# RFTX.net
KiCad netlist of a schematic drawn in Altium Designer
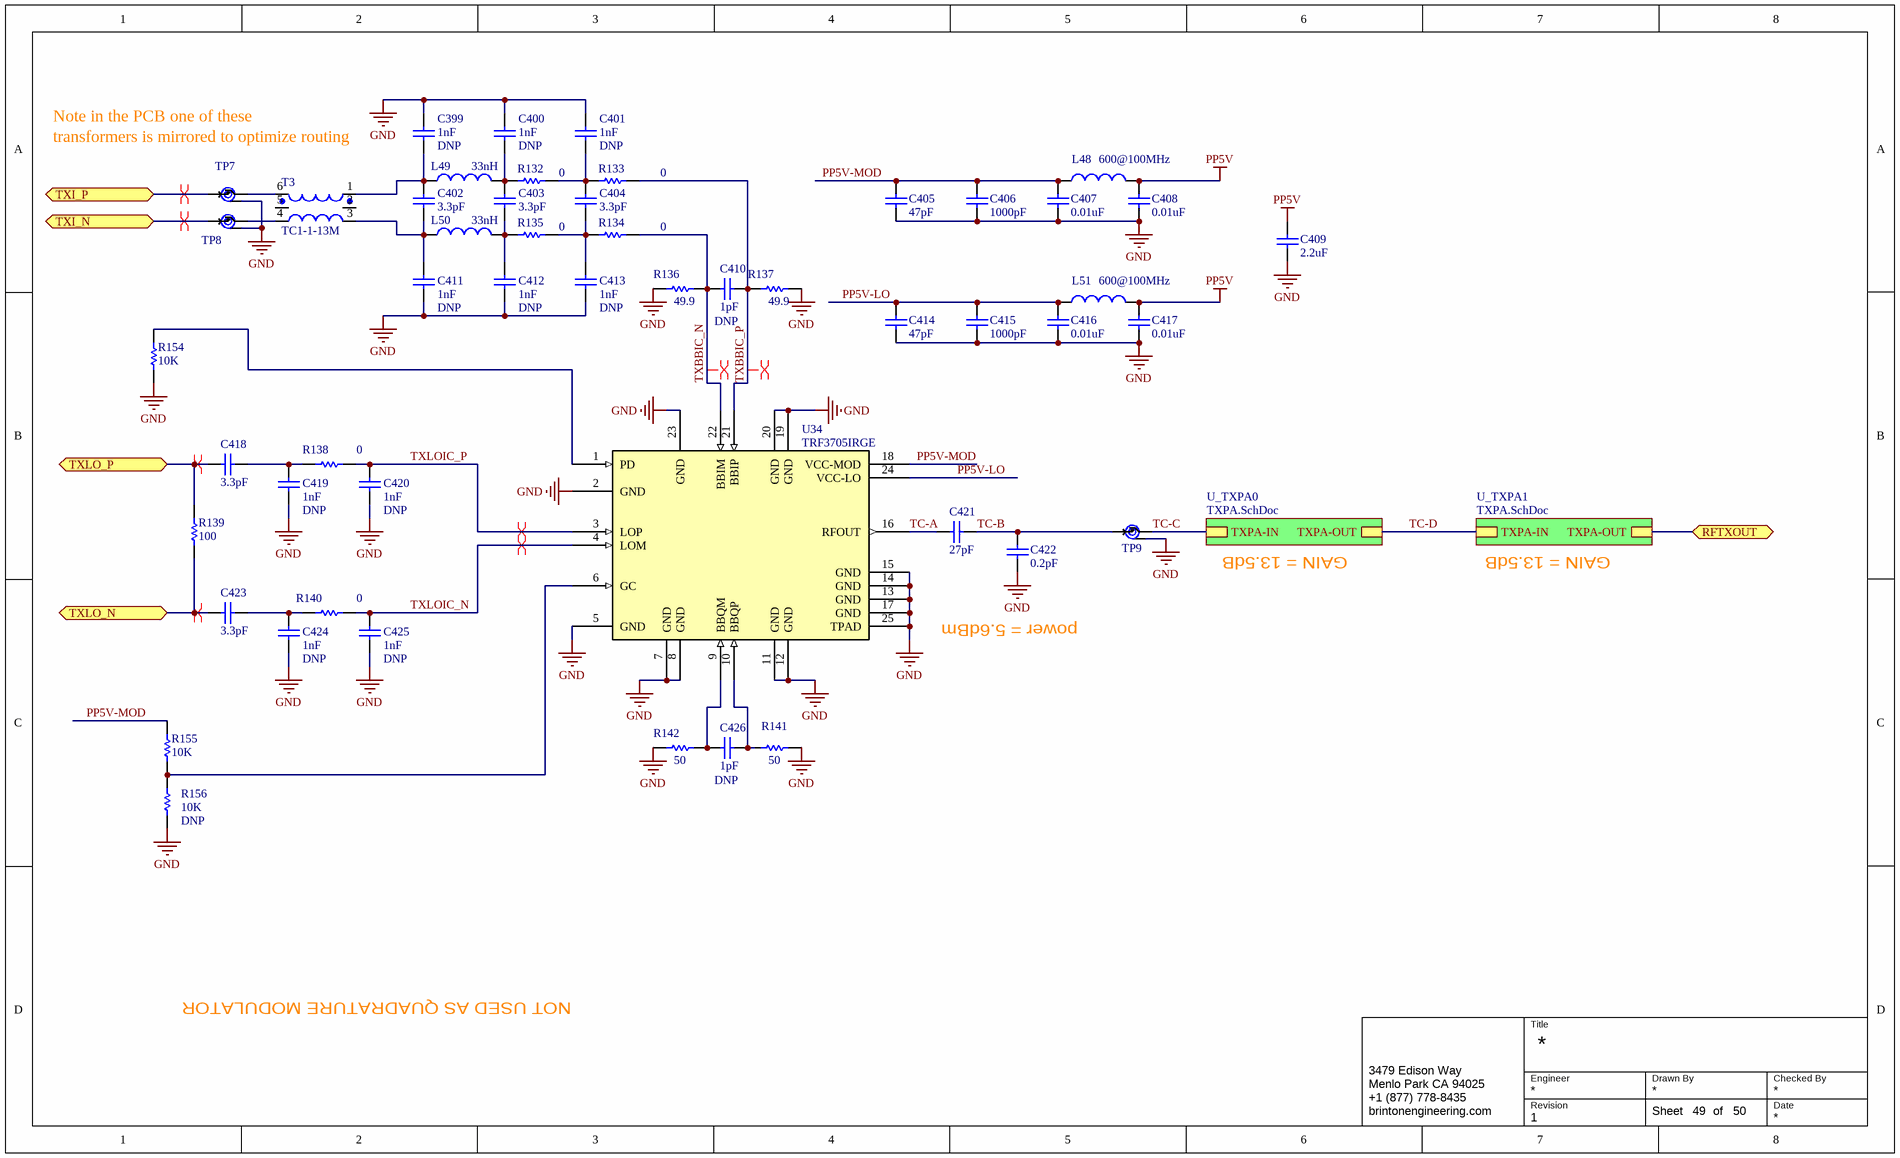
[diagram p0: RFTX.SchDoc]

(export (version "E")
  (design (tool "Eeschema 10.0.6"))
  (components
    (comp (ref "C399")
      (value "1nF")
      (footprint "0402")
      (description "CAP 0402")
      (fields (field (name "VOLTAGE") "16V") (field (name "DO NOT POPULATE") "DNP"))
      (libsource (lib "Graviton") (part "CAP 0402"))
    )
    (comp (ref "C400")
      (value "1nF")
      (footprint "0402")
      (description "CAP 0402")
      (fields (field (name "VOLTAGE") "16V") (field (name "DO NOT POPULATE") "DNP"))
      (libsource (lib "Graviton") (part "CAP 0402"))
    )
    (comp (ref "C401")
      (value "1nF")
      (footprint "0402")
      (description "CAP 0402")
      (fields (field (name "VOLTAGE") "16V") (field (name "DO NOT POPULATE") "DNP"))
      (libsource (lib "Graviton") (part "CAP 0402"))
    )
    (comp (ref "C402")
      (value "3.3pF")
      (footprint "0402")
      (description "CAP 0402")
      (fields (field (name "VOLTAGE") "50V") (field (name "MANUFACTURER") "Johanson Technology"))
      (libsource (lib "Graviton") (part "CAP 0402"))
    )
    (comp (ref "C403")
      (value "3.3pF")
      (footprint "0402")
      (description "CAP 0402")
      (fields (field (name "VOLTAGE") "50V") (field (name "MANUFACTURER") "Johanson Technology"))
      (libsource (lib "Graviton") (part "CAP 0402"))
    )
    (comp (ref "C404")
      (value "3.3pF")
      (footprint "0402")
      (description "CAP 0402")
      (fields (field (name "VOLTAGE") "50V") (field (name "MANUFACTURER") "Johanson Technology"))
      (libsource (lib "Graviton") (part "CAP 0402"))
    )
    (comp (ref "C405")
      (value "47pF")
      (footprint "0402")
      (description "CAP 0402")
      (fields (field (name "VOLTAGE") "25V") (field (name "MANUFACTURER") "Kemet"))
      (libsource (lib "Graviton") (part "CAP 0402"))
    )
    (comp (ref "C406")
      (value "1000pF")
      (footprint "0402")
      (description "CAP 0402")
      (fields (field (name "VOLTAGE") "50V") (field (name "MANUFACTURER") "Murata"))
      (libsource (lib "Graviton") (part "CAP 0402"))
    )
    (comp (ref "C407")
      (value "0.01uF")
      (footprint "0402")
      (description "CAP 0402")
      (fields (field (name "VOLTAGE") "25V") (field (name "MANUFACTURER") "Murata"))
      (libsource (lib "Graviton") (part "CAP 0402"))
    )
    (comp (ref "C408")
      (value "0.01uF")
      (footprint "0402")
      (description "CAP 0402")
      (fields (field (name "VOLTAGE") "25V") (field (name "MANUFACTURER") "Murata"))
      (libsource (lib "Graviton") (part "CAP 0402"))
    )
    (comp (ref "C409")
      (value "2.2uF")
      (footprint "1206")
      (description "CAP 0402")
      (fields (field (name "VOLTAGE") "16V") (field (name "MANUFACTURER") "Kemet"))
      (libsource (lib "Graviton") (part "CAP 0402"))
    )
    (comp (ref "C410")
      (value "1pF")
      (footprint "0402")
      (description "CAP 0402")
      (fields (field (name "VOLTAGE") "16V") (field (name "DO NOT POPULATE") "DNP"))
      (libsource (lib "Graviton") (part "CAP 0402"))
    )
    (comp (ref "C411")
      (value "1nF")
      (footprint "0402")
      (description "CAP 0402")
      (fields (field (name "VOLTAGE") "16V") (field (name "DO NOT POPULATE") "DNP"))
      (libsource (lib "Graviton") (part "CAP 0402"))
    )
    (comp (ref "C412")
      (value "1nF")
      (footprint "0402")
      (description "CAP 0402")
      (fields (field (name "VOLTAGE") "16V") (field (name "DO NOT POPULATE") "DNP"))
      (libsource (lib "Graviton") (part "CAP 0402"))
    )
    (comp (ref "C413")
      (value "1nF")
      (footprint "0402")
      (description "CAP 0402")
      (fields (field (name "VOLTAGE") "16V") (field (name "DO NOT POPULATE") "DNP"))
      (libsource (lib "Graviton") (part "CAP 0402"))
    )
    (comp (ref "C414")
      (value "47pF")
      (footprint "0402")
      (description "CAP 0402")
      (fields (field (name "VOLTAGE") "25V") (field (name "MANUFACTURER") "Kemet"))
      (libsource (lib "Graviton") (part "CAP 0402"))
    )
    (comp (ref "C415")
      (value "1000pF")
      (footprint "0402")
      (description "CAP 0402")
      (fields (field (name "VOLTAGE") "50V") (field (name "MANUFACTURER") "Murata"))
      (libsource (lib "Graviton") (part "CAP 0402"))
    )
    (comp (ref "C416")
      (value "0.01uF")
      (footprint "0402")
      (description "CAP 0402")
      (fields (field (name "VOLTAGE") "25V") (field (name "MANUFACTURER") "Murata"))
      (libsource (lib "Graviton") (part "CAP 0402"))
    )
    (comp (ref "C417")
      (value "0.01uF")
      (footprint "0402")
      (description "CAP 0402")
      (fields (field (name "VOLTAGE") "25V") (field (name "MANUFACTURER") "Murata"))
      (libsource (lib "Graviton") (part "CAP 0402"))
    )
    (comp (ref "C418")
      (value "3.3pF")
      (footprint "0402")
      (description "CAP 0402")
      (fields (field (name "VOLTAGE") "50V") (field (name "MANUFACTURER") "Johanson Technology"))
      (libsource (lib "Graviton") (part "CAP 0402"))
    )
    (comp (ref "C419")
      (value "1nF")
      (footprint "0402")
      (description "CAP 0402")
      (fields (field (name "VOLTAGE") "16V") (field (name "DO NOT POPULATE") "DNP"))
      (libsource (lib "Graviton") (part "CAP 0402"))
    )
    (comp (ref "C420")
      (value "1nF")
      (footprint "0402")
      (description "CAP 0402")
      (fields (field (name "VOLTAGE") "16V") (field (name "DO NOT POPULATE") "DNP"))
      (libsource (lib "Graviton") (part "CAP 0402"))
    )
    (comp (ref "C421")
      (value "27pF")
      (footprint "0402")
      (description "CAP 0402")
      (fields (field (name "VOLTAGE") "200V") (field (name "MANUFACTURER") "American Technical Ceramics"))
      (libsource (lib "Graviton") (part "CAP 0402"))
    )
    (comp (ref "C422")
      (value "0.2pF")
      (footprint "0402")
      (description "CAP 0402")
      (fields (field (name "VOLTAGE") "16V"))
      (libsource (lib "Graviton") (part "CAP 0402"))
    )
    (comp (ref "C423")
      (value "3.3pF")
      (footprint "0402")
      (description "CAP 0402")
      (fields (field (name "VOLTAGE") "50V") (field (name "MANUFACTURER") "Johanson Technology"))
      (libsource (lib "Graviton") (part "CAP 0402"))
    )
    (comp (ref "C424")
      (value "1nF")
      (footprint "0402")
      (description "CAP 0402")
      (fields (field (name "VOLTAGE") "16V") (field (name "DO NOT POPULATE") "DNP"))
      (libsource (lib "Graviton") (part "CAP 0402"))
    )
    (comp (ref "C425")
      (value "1nF")
      (footprint "0402")
      (description "CAP 0402")
      (fields (field (name "VOLTAGE") "16V") (field (name "DO NOT POPULATE") "DNP"))
      (libsource (lib "Graviton") (part "CAP 0402"))
    )
    (comp (ref "C426")
      (value "1pF")
      (footprint "0402")
      (description "CAP 0402")
      (fields (field (name "VOLTAGE") "16V") (field (name "DO NOT POPULATE") "DNP"))
      (libsource (lib "Graviton") (part "CAP 0402"))
    )
    (comp (ref "L48")
      (value "600@100MHz")
      (footprint "0402")
      (description "Inductor")
      (fields (field (name "MANUFACTURER") "Murata") (field (name "Comment") "IND 0402"))
      (libsource (lib "Graviton") (part "IND 0402"))
    )
    (comp (ref "L49")
      (value "33nH")
      (footprint "0603")
      (description "Inductor")
      (fields (field (name "MANUFACTURER") "Murata") (field (name "Comment") "IND 0603"))
      (libsource (lib "Graviton") (part "IND 0603"))
    )
    (comp (ref "L50")
      (value "33nH")
      (footprint "0603")
      (description "Inductor")
      (fields (field (name "MANUFACTURER") "Murata") (field (name "Comment") "IND 0603"))
      (libsource (lib "Graviton") (part "IND 0603"))
    )
    (comp (ref "L51")
      (value "600@100MHz")
      (footprint "0402")
      (description "Inductor")
      (fields (field (name "MANUFACTURER") "Murata") (field (name "Comment") "IND 0402"))
      (libsource (lib "Graviton") (part "IND 0402"))
    )
    (comp (ref "R132")
      (value "0")
      (footprint "0402")
      (description "Resistor, SMD 0402")
      (fields (field (name "Comment") "RES 0402"))
      (libsource (lib "generic") (part "RES 0402"))
    )
    (comp (ref "R133")
      (value "0")
      (footprint "0402")
      (description "Resistor, SMD 0402")
      (fields (field (name "Comment") "RES 0402"))
      (libsource (lib "generic") (part "RES 0402"))
    )
    (comp (ref "R134")
      (value "0")
      (footprint "0402")
      (description "Resistor, SMD 0402")
      (fields (field (name "Comment") "RES 0402"))
      (libsource (lib "generic") (part "RES 0402"))
    )
    (comp (ref "R135")
      (value "0")
      (footprint "0402")
      (description "Resistor, SMD 0402")
      (fields (field (name "Comment") "RES 0402"))
      (libsource (lib "generic") (part "RES 0402"))
    )
    (comp (ref "R136")
      (value "49.9")
      (footprint "0402")
      (description "Resistor, SMD 0402")
      (fields (field (name "MANUFACTURER") "Panasonic") (field (name "Comment") "RES 0402"))
      (libsource (lib "Graviton") (part "RES 0402"))
    )
    (comp (ref "R137")
      (value "49.9")
      (footprint "0402")
      (description "Resistor, SMD 0402")
      (fields (field (name "MANUFACTURER") "Panasonic") (field (name "Comment") "RES 0402"))
      (libsource (lib "Graviton") (part "RES 0402"))
    )
    (comp (ref "R138")
      (value "0")
      (footprint "0402")
      (description "Resistor, SMD 0402")
      (fields (field (name "Comment") "RES 0402"))
      (libsource (lib "generic") (part "RES 0402"))
    )
    (comp (ref "R139")
      (value "100")
      (footprint "0402")
      (description "Resistor, SMD 0402")
      (fields (field (name "Comment") "RES 0402"))
      (libsource (lib "generic") (part "RES 0402"))
    )
    (comp (ref "R140")
      (value "0")
      (footprint "0402")
      (description "Resistor, SMD 0402")
      (fields (field (name "Comment") "RES 0402"))
      (libsource (lib "generic") (part "RES 0402"))
    )
    (comp (ref "R141")
      (value "50")
      (footprint "0402")
      (description "Resistor, SMD 0402")
      (fields (field (name "Comment") "RES 0402"))
      (libsource (lib "Graviton") (part "RES 0402"))
    )
    (comp (ref "R142")
      (value "50")
      (footprint "0402")
      (description "Resistor, SMD 0402")
      (fields (field (name "Comment") "RES 0402"))
      (libsource (lib "Graviton") (part "RES 0402"))
    )
    (comp (ref "R154")
      (value "10K")
      (footprint "0402")
      (description "Resistor, SMD 0402")
      (fields (field (name "Comment") "RES 0402"))
      (libsource (lib "Graviton") (part "RES 0402"))
    )
    (comp (ref "R155")
      (value "10K")
      (footprint "0402")
      (description "Resistor, SMD 0402")
      (fields (field (name "Comment") "RES 0402"))
      (libsource (lib "Graviton") (part "RES 0402"))
    )
    (comp (ref "R156")
      (value "10K")
      (footprint "0402")
      (description "Resistor, SMD 0402")
      (fields (field (name "DO NOT POPULATE") "DNP") (field (name "Comment") "RES 0402"))
      (libsource (lib "Graviton") (part "RES 0402"))
    )
    (comp (ref "T3")
      (value "TC1-1-13M")
      (footprint "AT224-1A")
      (description "RF Transformer 4-3000KHz 50 ohms")
      (fields (field (name "MANUFACTURER") "Mini-Circuits"))
      (libsource (lib "Mini-Circuits") (part "TC1-1-13M"))
    )
    (comp (ref "TP7")
      (value "MS-180(20)")
      (footprint "MS-180(20)")
      (description "Coaxial Connector Switch")
      (fields (field (name "MANUFACTURER") "Hirose"))
      (libsource (lib "hirose") (part "MS-180(20)"))
    )
    (comp (ref "TP8")
      (value "MS-180(20)")
      (footprint "MS-180(20)")
      (description "Coaxial Connector Switch")
      (fields (field (name "MANUFACTURER") "Hirose"))
      (libsource (lib "hirose") (part "MS-180(20)"))
    )
    (comp (ref "TP9")
      (value "MS-180(20)")
      (footprint "MS-180(20)")
      (description "Coaxial Connector Switch")
      (fields (field (name "MANUFACTURER") "Hirose"))
      (libsource (lib "hirose") (part "MS-180(20)"))
    )
    (comp (ref "U34")
      (value "TRF3705_RGE_24")
      (footprint "RGE-VQFN-24")
      (description "300MHz to 4GHz Quadrature Modulator")
      (fields
        (field (name "GENERIC_PART_NUMBER") "TRF3705")
        (field (name "MANUFACTURER") "Texas Instruments")
        (field (name "MANUFACTURER P/N") "TRF3705IRGE")
      )
      (libsource (lib "ti") (part "TRF3705_RGE_24"))
    )
  )
  (nets
    (net (code "1") (name "/PP5V-LO") (class "Default")
      (node (ref "C414") (pin "2") (pinfunction "2_2") (pintype "passive"))
      (node (ref "C415") (pin "2") (pinfunction "2_2") (pintype "passive"))
      (node (ref "C416") (pin "2") (pinfunction "2_2") (pintype "passive"))
      (node (ref "L51") (pin "2") (pinfunction "2_2") (pintype "passive"))
      (node (ref "U34") (pin "24") (pinfunction "VCC-LO_24") (pintype "power_in"))
    )
    (net (code "2") (name "/PP5V-MOD") (class "Default")
      (node (ref "C405") (pin "2") (pinfunction "2_2") (pintype "passive"))
      (node (ref "C406") (pin "2") (pinfunction "2_2") (pintype "passive"))
      (node (ref "C407") (pin "2") (pinfunction "2_2") (pintype "passive"))
      (node (ref "L48") (pin "2") (pinfunction "2_2") (pintype "passive"))
      (node (ref "R155") (pin "1") (pinfunction "1_1") (pintype "passive"))
      (node (ref "U34") (pin "18") (pinfunction "VCC-MOD_18") (pintype "power_in"))
    )
    (net (code "4") (name "/TC-A") (class "Default")
      (node (ref "C421") (pin "1") (pinfunction "1_1") (pintype "passive"))
      (node (ref "U34") (pin "16") (pinfunction "RFOUT_16") (pintype "output"))
    )
    (net (code "5") (name "/TC-B") (class "Default")
      (node (ref "C421") (pin "2") (pinfunction "2_2") (pintype "passive"))
      (node (ref "C422") (pin "2") (pinfunction "2_2") (pintype "passive"))
      (node (ref "TP9") (pin "C") (pinfunction "IN_C") (pintype "passive"))
    )
    (net (code "6") (name "/TC-C") (class "Default")
      (node (ref "TP9") (pin "A") (pinfunction "OUT_A") (pintype "passive"))
    )
    (net (code "8") (name "/TXBBIC_N") (class "Default")
      (node (ref "C410") (pin "1") (pinfunction "1_1") (pintype "passive"))
      (node (ref "R134") (pin "2") (pinfunction "2_2") (pintype "passive"))
      (node (ref "R136") (pin "1") (pinfunction "1_1") (pintype "passive"))
      (node (ref "U34") (pin "22") (pinfunction "BBIM_22") (pintype "input"))
    )
    (net (code "9") (name "/TXBBIC_P") (class "Default")
      (node (ref "C410") (pin "2") (pinfunction "2_2") (pintype "passive"))
      (node (ref "R133") (pin "2") (pinfunction "2_2") (pintype "passive"))
      (node (ref "R137") (pin "2") (pinfunction "2_2") (pintype "passive"))
      (node (ref "U34") (pin "21") (pinfunction "BBIP_21") (pintype "input"))
    )
    (net (code "10") (name "/TXI_N") (class "Default")
      (node (ref "TP8") (pin "C") (pinfunction "IN_C") (pintype "passive"))
    )
    (net (code "11") (name "/TXI_P") (class "Default")
      (node (ref "TP7") (pin "C") (pinfunction "IN_C") (pintype "passive"))
    )
    (net (code "12") (name "/TXLOIC_N") (class "Default")
      (node (ref "C425") (pin "2") (pinfunction "2_2") (pintype "passive"))
      (node (ref "R140") (pin "2") (pinfunction "2_2") (pintype "passive"))
      (node (ref "U34") (pin "4") (pinfunction "LOM_4") (pintype "input"))
    )
    (net (code "13") (name "/TXLOIC_P") (class "Default")
      (node (ref "C420") (pin "2") (pinfunction "2_2") (pintype "passive"))
      (node (ref "R138") (pin "2") (pinfunction "2_2") (pintype "passive"))
      (node (ref "U34") (pin "3") (pinfunction "LOP_3") (pintype "input"))
    )
    (net (code "14") (name "/TXLO_N") (class "Default")
      (node (ref "C423") (pin "2") (pinfunction "2_2") (pintype "passive"))
      (node (ref "R139") (pin "1") (pinfunction "1_1") (pintype "passive"))
    )
    (net (code "15") (name "/TXLO_P") (class "Default")
      (node (ref "C418") (pin "2") (pinfunction "2_2") (pintype "passive"))
      (node (ref "R139") (pin "2") (pinfunction "2_2") (pintype "passive"))
    )
    (net (code "16") (name "GND") (class "Default")
      (node (ref "C399") (pin "1") (pinfunction "1_1") (pintype "passive"))
      (node (ref "C400") (pin "1") (pinfunction "1_1") (pintype "passive"))
      (node (ref "C401") (pin "1") (pinfunction "1_1") (pintype "passive"))
      (node (ref "C405") (pin "1") (pinfunction "1_1") (pintype "passive"))
      (node (ref "C406") (pin "1") (pinfunction "1_1") (pintype "passive"))
      (node (ref "C407") (pin "1") (pinfunction "1_1") (pintype "passive"))
      (node (ref "C408") (pin "1") (pinfunction "1_1") (pintype "passive"))
      (node (ref "C409") (pin "1") (pinfunction "1_1") (pintype "passive"))
      (node (ref "C411") (pin "1") (pinfunction "1_1") (pintype "passive"))
      (node (ref "C412") (pin "1") (pinfunction "1_1") (pintype "passive"))
      (node (ref "C413") (pin "1") (pinfunction "1_1") (pintype "passive"))
      (node (ref "C414") (pin "1") (pinfunction "1_1") (pintype "passive"))
      (node (ref "C415") (pin "1") (pinfunction "1_1") (pintype "passive"))
      (node (ref "C416") (pin "1") (pinfunction "1_1") (pintype "passive"))
      (node (ref "C417") (pin "1") (pinfunction "1_1") (pintype "passive"))
      (node (ref "C419") (pin "1") (pinfunction "1_1") (pintype "passive"))
      (node (ref "C420") (pin "1") (pinfunction "1_1") (pintype "passive"))
      (node (ref "C422") (pin "1") (pinfunction "1_1") (pintype "passive"))
      (node (ref "C424") (pin "1") (pinfunction "1_1") (pintype "passive"))
      (node (ref "C425") (pin "1") (pinfunction "1_1") (pintype "passive"))
      (node (ref "R136") (pin "2") (pinfunction "2_2") (pintype "passive"))
      (node (ref "R137") (pin "1") (pinfunction "1_1") (pintype "passive"))
      (node (ref "R141") (pin "1") (pinfunction "1_1") (pintype "passive"))
      (node (ref "R142") (pin "2") (pinfunction "2_2") (pintype "passive"))
      (node (ref "R154") (pin "2") (pinfunction "2_2") (pintype "passive"))
      (node (ref "R156") (pin "2") (pinfunction "2_2") (pintype "passive"))
      (node (ref "TP7") (pin "G") (pinfunction "GND_G") (pintype "passive"))
      (node (ref "TP8") (pin "G") (pinfunction "GND_G") (pintype "passive"))
      (node (ref "TP9") (pin "G") (pinfunction "GND_G") (pintype "passive"))
      (node (ref "U34") (pin "11") (pinfunction "GND_11") (pintype "power_in"))
      (node (ref "U34") (pin "12") (pinfunction "GND_12") (pintype "power_in"))
      (node (ref "U34") (pin "13") (pinfunction "GND_13") (pintype "power_in"))
      (node (ref "U34") (pin "14") (pinfunction "GND_14") (pintype "power_in"))
      (node (ref "U34") (pin "15") (pinfunction "GND_15") (pintype "power_in"))
      (node (ref "U34") (pin "17") (pinfunction "GND_17") (pintype "power_in"))
      (node (ref "U34") (pin "19") (pinfunction "GND_19") (pintype "power_in"))
      (node (ref "U34") (pin "2") (pinfunction "GND_2") (pintype "power_in"))
      (node (ref "U34") (pin "20") (pinfunction "GND_20") (pintype "power_in"))
      (node (ref "U34") (pin "23") (pinfunction "GND_23") (pintype "power_in"))
      (node (ref "U34") (pin "25") (pinfunction "TPAD_25") (pintype "passive"))
      (node (ref "U34") (pin "5") (pinfunction "GND_5") (pintype "power_in"))
      (node (ref "U34") (pin "7") (pinfunction "GND_7") (pintype "power_in"))
      (node (ref "U34") (pin "8") (pinfunction "GND_8") (pintype "power_in"))
    )
    (net (code "17") (name "Net-(C399-Pad2)") (class "Default")
      (node (ref "C399") (pin "2") (pinfunction "2_2") (pintype "passive"))
      (node (ref "C402") (pin "2") (pinfunction "2_2") (pintype "passive"))
      (node (ref "L49") (pin "1") (pinfunction "1_1") (pintype "passive"))
      (node (ref "T3") (pin "1") (pinfunction "1_1") (pintype "passive"))
    )
    (net (code "18") (name "Net-(C400-Pad2)") (class "Default")
      (node (ref "C400") (pin "2") (pinfunction "2_2") (pintype "passive"))
      (node (ref "C403") (pin "2") (pinfunction "2_2") (pintype "passive"))
      (node (ref "L49") (pin "2") (pinfunction "2_2") (pintype "passive"))
      (node (ref "R132") (pin "1") (pinfunction "1_1") (pintype "passive"))
    )
    (net (code "19") (name "Net-(C401-Pad2)") (class "Default")
      (node (ref "C401") (pin "2") (pinfunction "2_2") (pintype "passive"))
      (node (ref "C404") (pin "2") (pinfunction "2_2") (pintype "passive"))
      (node (ref "R132") (pin "2") (pinfunction "2_2") (pintype "passive"))
      (node (ref "R133") (pin "1") (pinfunction "1_1") (pintype "passive"))
    )
    (net (code "20") (name "Net-(C402-Pad1)") (class "Default")
      (node (ref "C402") (pin "1") (pinfunction "1_1") (pintype "passive"))
      (node (ref "C411") (pin "2") (pinfunction "2_2") (pintype "passive"))
      (node (ref "L50") (pin "1") (pinfunction "1_1") (pintype "passive"))
      (node (ref "T3") (pin "3") (pinfunction "3_3") (pintype "passive"))
    )
    (net (code "21") (name "Net-(C403-Pad1)") (class "Default")
      (node (ref "C403") (pin "1") (pinfunction "1_1") (pintype "passive"))
      (node (ref "C412") (pin "2") (pinfunction "2_2") (pintype "passive"))
      (node (ref "L50") (pin "2") (pinfunction "2_2") (pintype "passive"))
      (node (ref "R135") (pin "1") (pinfunction "1_1") (pintype "passive"))
    )
    (net (code "22") (name "Net-(C404-Pad1)") (class "Default")
      (node (ref "C404") (pin "1") (pinfunction "1_1") (pintype "passive"))
      (node (ref "C413") (pin "2") (pinfunction "2_2") (pintype "passive"))
      (node (ref "R134") (pin "1") (pinfunction "1_1") (pintype "passive"))
      (node (ref "R135") (pin "2") (pinfunction "2_2") (pintype "passive"))
    )
    (net (code "23") (name "Net-(C418-Pad1)") (class "Default")
      (node (ref "C418") (pin "1") (pinfunction "1_1") (pintype "passive"))
      (node (ref "C419") (pin "2") (pinfunction "2_2") (pintype "passive"))
      (node (ref "R138") (pin "1") (pinfunction "1_1") (pintype "passive"))
    )
    (net (code "24") (name "Net-(C423-Pad1)") (class "Default")
      (node (ref "C423") (pin "1") (pinfunction "1_1") (pintype "passive"))
      (node (ref "C424") (pin "2") (pinfunction "2_2") (pintype "passive"))
      (node (ref "R140") (pin "1") (pinfunction "1_1") (pintype "passive"))
    )
    (net (code "25") (name "Net-(TP7-OUT)") (class "Default")
      (node (ref "T3") (pin "6") (pinfunction "6_6") (pintype "passive"))
      (node (ref "TP7") (pin "A") (pinfunction "OUT_A") (pintype "passive"))
    )
    (net (code "26") (name "Net-(TP8-OUT)") (class "Default")
      (node (ref "T3") (pin "4") (pinfunction "4_4") (pintype "passive"))
      (node (ref "TP8") (pin "A") (pinfunction "OUT_A") (pintype "passive"))
    )
    (net (code "27") (name "Net-(U34-BBQM)") (class "Default")
      (node (ref "C426") (pin "1") (pinfunction "1_1") (pintype "passive"))
      (node (ref "R142") (pin "1") (pinfunction "1_1") (pintype "passive"))
      (node (ref "U34") (pin "9") (pinfunction "BBQM_9") (pintype "input"))
    )
    (net (code "28") (name "Net-(U34-BBQP)") (class "Default")
      (node (ref "C426") (pin "2") (pinfunction "2_2") (pintype "passive"))
      (node (ref "R141") (pin "2") (pinfunction "2_2") (pintype "passive"))
      (node (ref "U34") (pin "10") (pinfunction "BBQP_10") (pintype "input"))
    )
    (net (code "29") (name "Net-(U34-GC)") (class "Default")
      (node (ref "R155") (pin "2") (pinfunction "2_2") (pintype "passive"))
      (node (ref "R156") (pin "1") (pinfunction "1_1") (pintype "passive"))
      (node (ref "U34") (pin "6") (pinfunction "GC_6") (pintype "input"))
    )
    (net (code "30") (name "Net-(U34-PD)") (class "Default")
      (node (ref "R154") (pin "1") (pinfunction "1_1") (pintype "passive"))
      (node (ref "U34") (pin "1") (pinfunction "PD_1") (pintype "input"))
    )
    (net (code "31") (name "PP5V") (class "Default")
      (node (ref "C408") (pin "2") (pinfunction "2_2") (pintype "passive"))
      (node (ref "C409") (pin "2") (pinfunction "2_2") (pintype "passive"))
      (node (ref "C417") (pin "2") (pinfunction "2_2") (pintype "passive"))
      (node (ref "L48") (pin "1") (pinfunction "1_1") (pintype "passive"))
      (node (ref "L51") (pin "1") (pinfunction "1_1") (pintype "passive"))
    )
    (net (code "32") (name "unconnected-(T3-Pad2)") (class "Default")
      (node (ref "T3") (pin "2") (pinfunction "2_2") (pintype "passive"))
    )
    (net (code "33") (name "unconnected-(T3-Pad5)") (class "Default")
      (node (ref "T3") (pin "5") (pinfunction "5_5") (pintype "passive"))
    )
  )
)
